# SCH_AD741-discrete_2022-10-03.net
KiCad netlist of a schematic drawn in EasyEDA
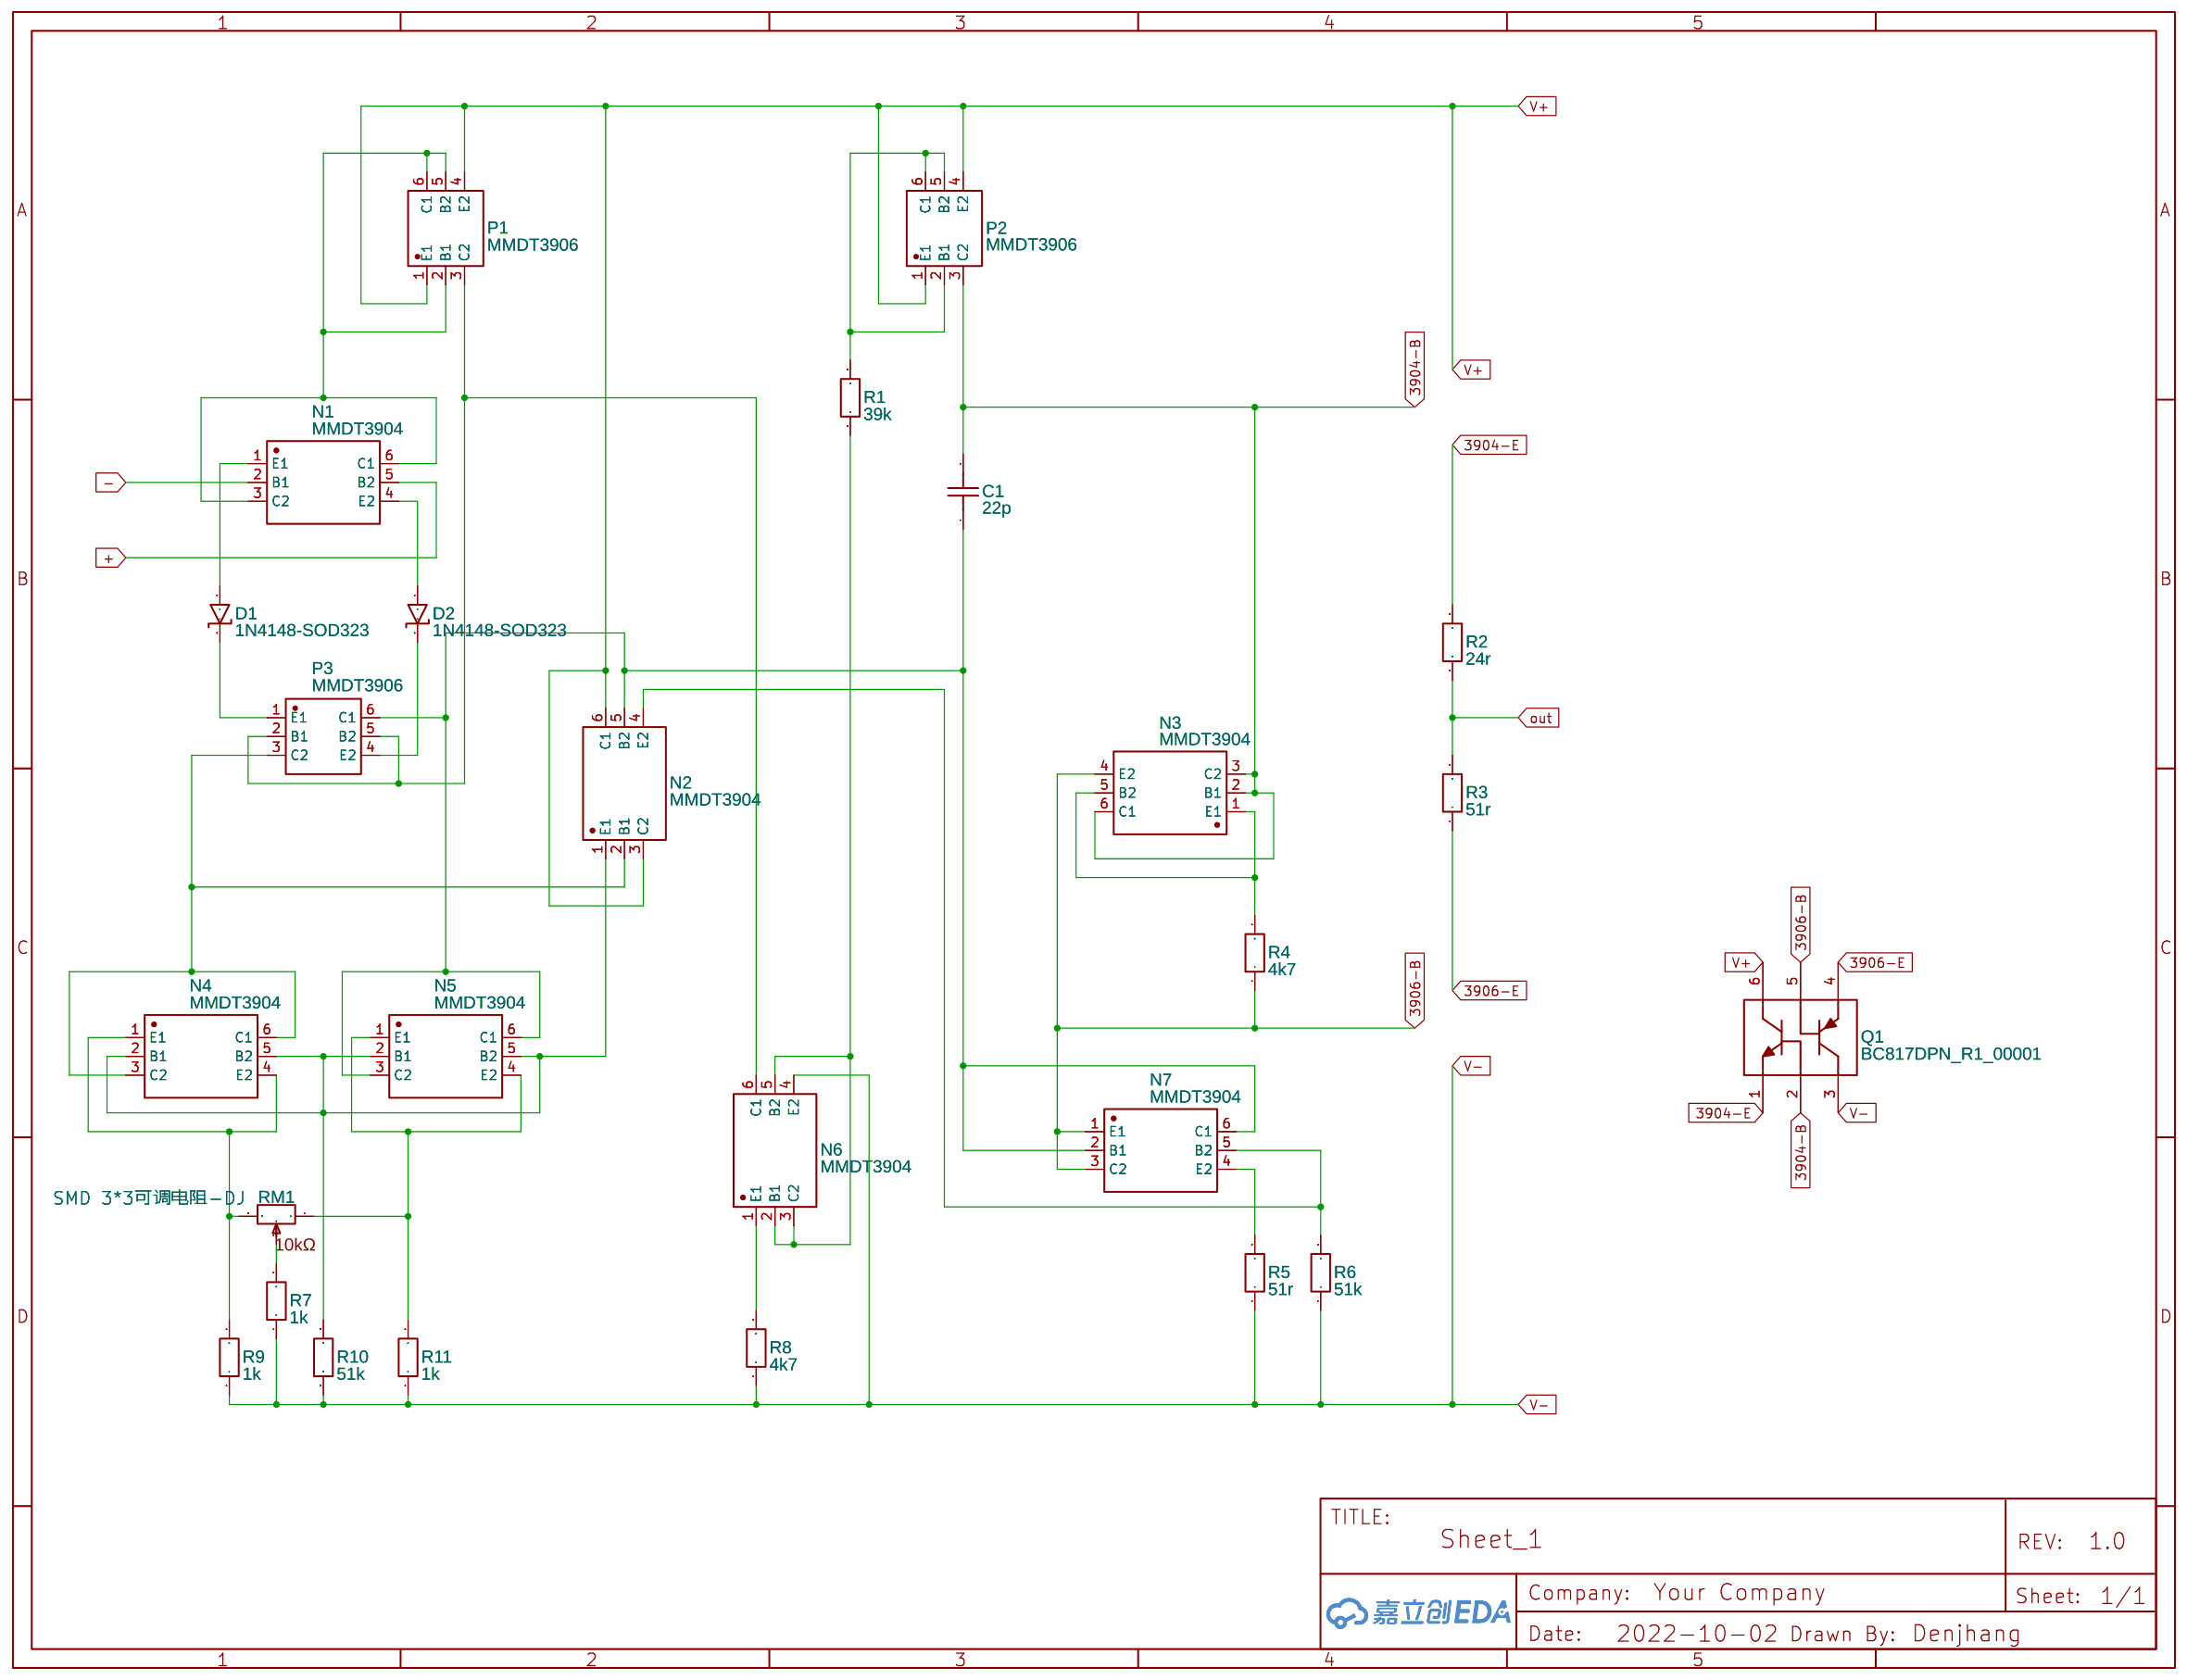
[diagram p0: P1]
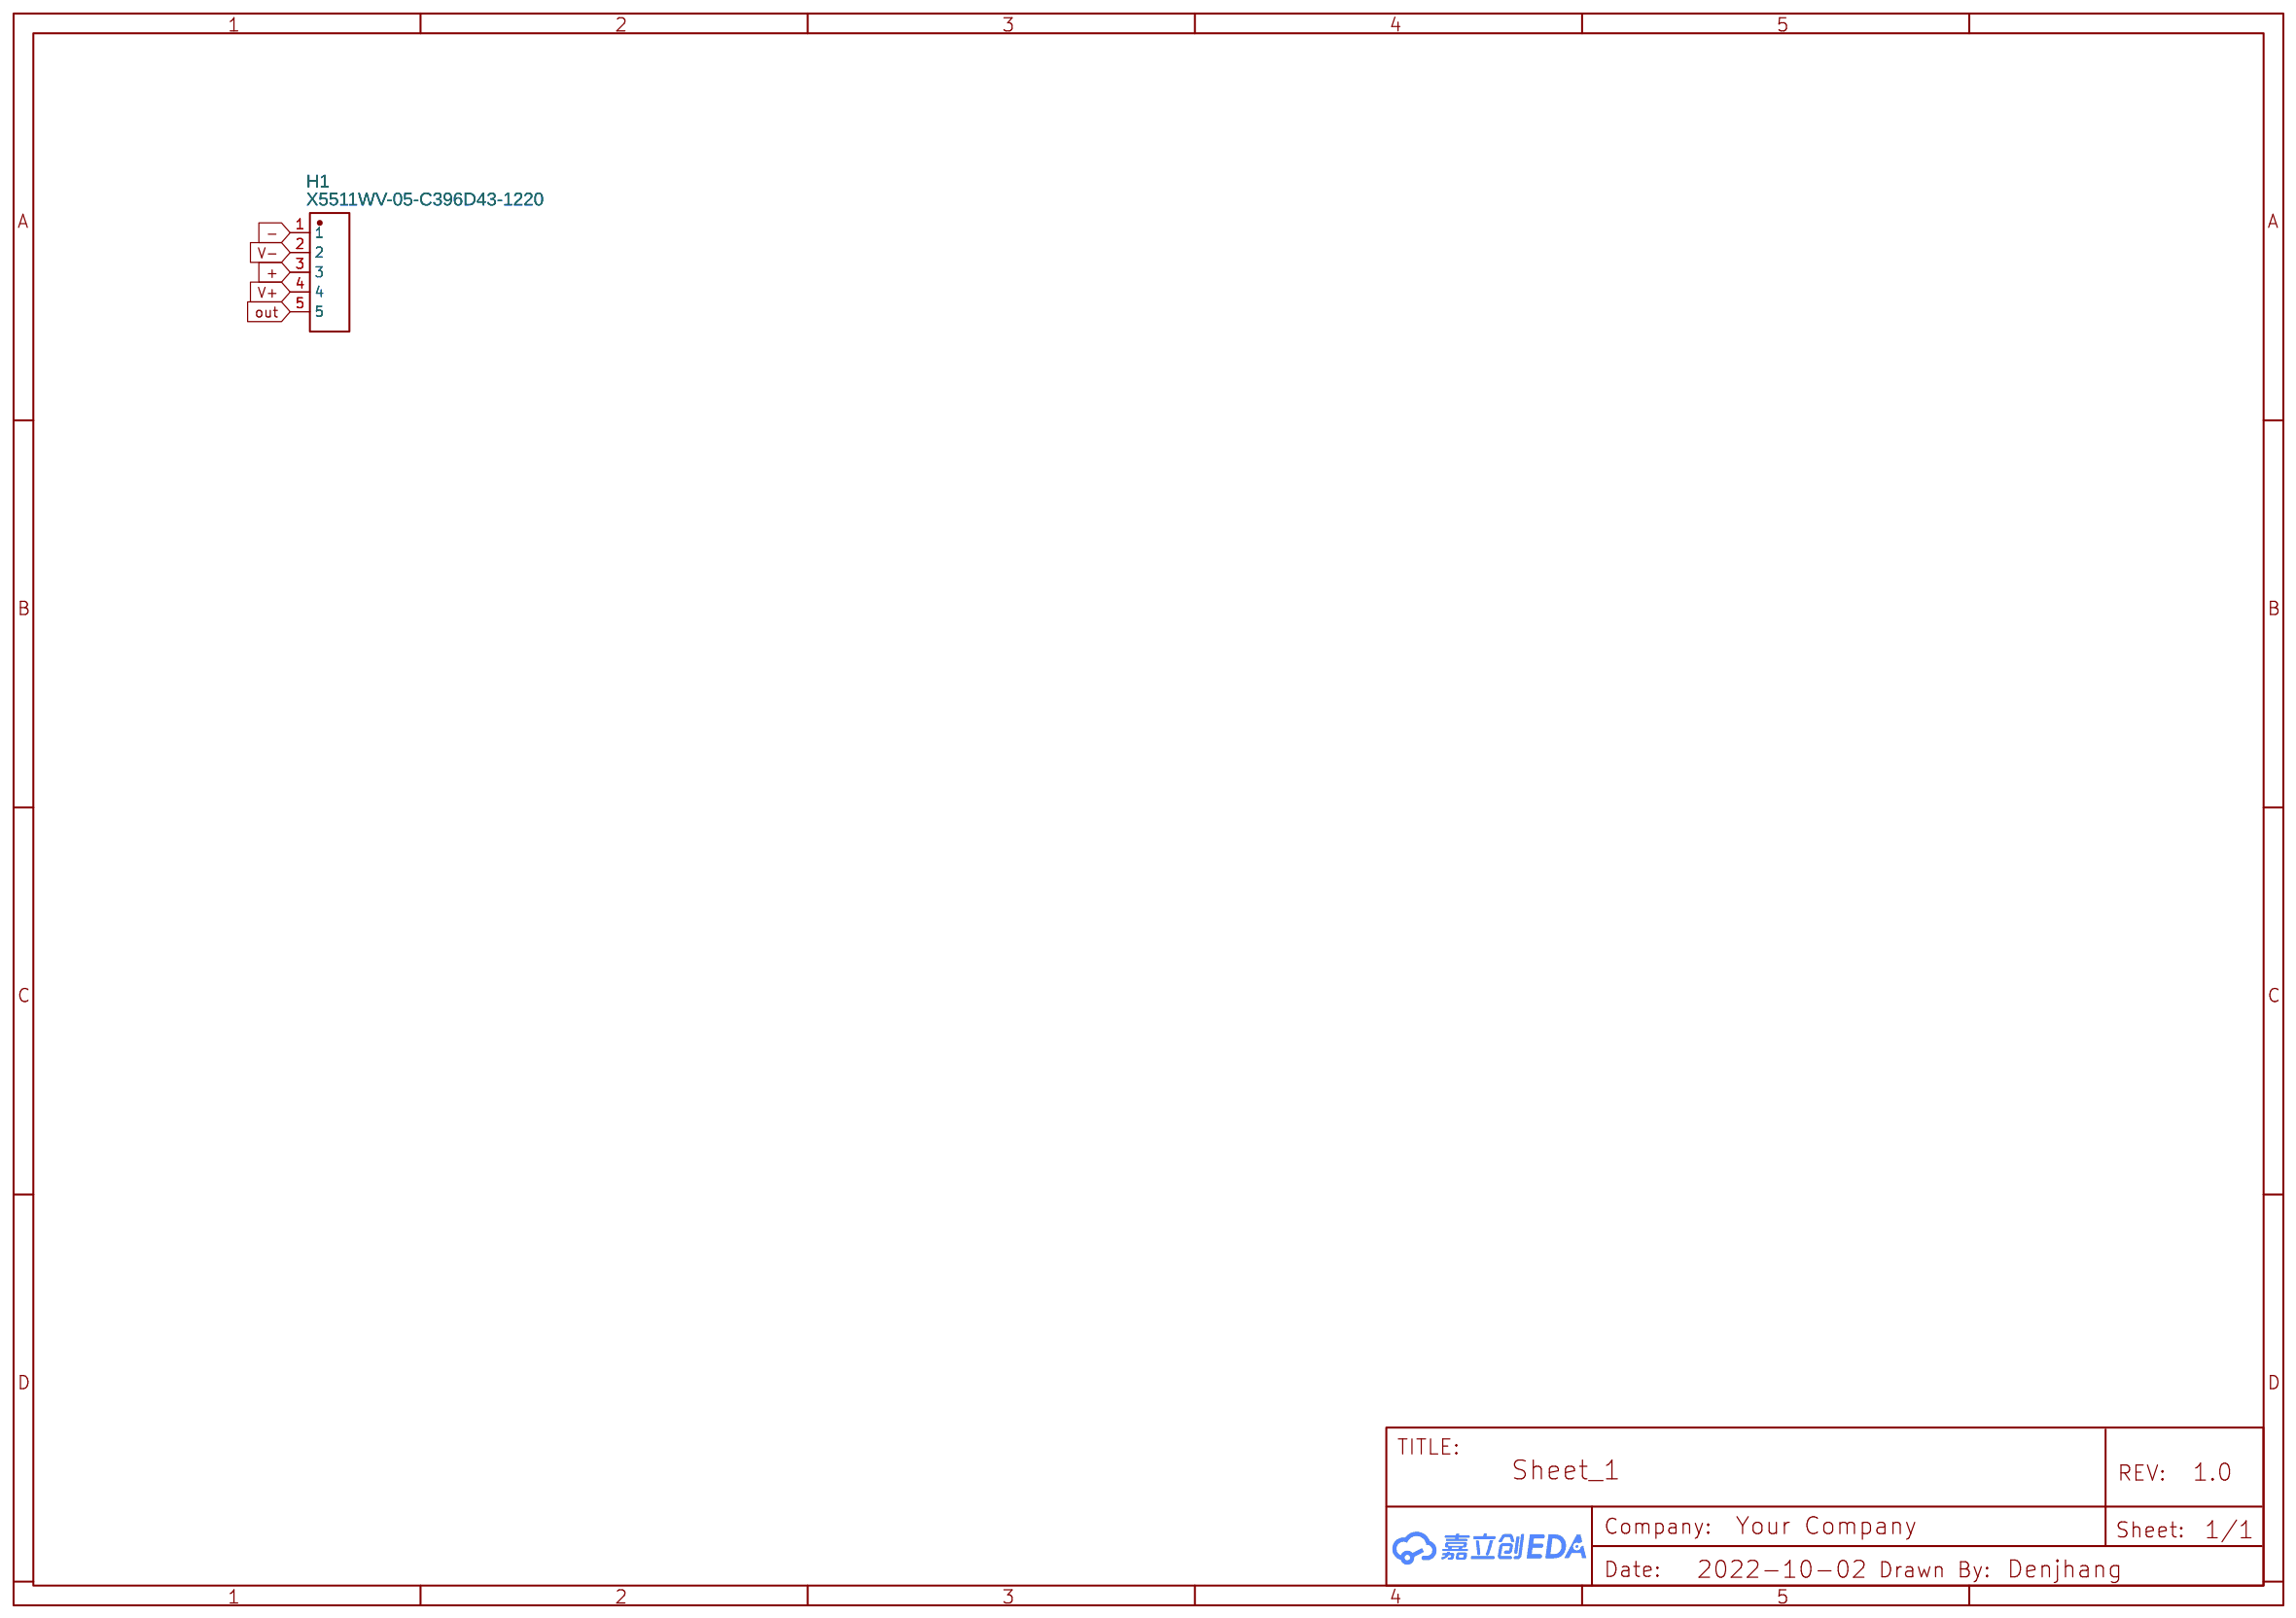
[diagram p1: CONN]

(export (version "E")
  (design (tool "Eeschema 10.0.6"))
  (components
    (comp (ref "C1") (value "22p") (libsource (lib "") (part "C_0603_US")))
    (comp (ref "D1")
      (value "1N4148-SOD323")
      (fields (field (name "BOM_Supplier Part") "C9900014362"))
      (libsource (lib "") (part "1N4148-SOD323"))
    )
    (comp (ref "D2")
      (value "1N4148-SOD323")
      (fields (field (name "BOM_Supplier Part") "C9900014362"))
      (libsource (lib "") (part "1N4148-SOD323"))
    )
    (comp (ref "N1")
      (value "MMDT3904")
      (fields (field (name "BOM_Supplier Part") "C21664"))
      (libsource (lib "") (part "MMDT3904"))
    )
    (comp (ref "N2")
      (value "MMDT3904")
      (fields (field (name "BOM_Supplier Part") "C21664"))
      (libsource (lib "") (part "MMDT3904_1"))
    )
    (comp (ref "N3")
      (value "MMDT3904")
      (fields (field (name "BOM_Supplier Part") "C21664"))
      (libsource (lib "") (part "MMDT3904_2"))
    )
    (comp (ref "N4")
      (value "MMDT3904")
      (fields (field (name "BOM_Supplier Part") "C21664"))
      (libsource (lib "") (part "MMDT3904"))
    )
    (comp (ref "N5")
      (value "MMDT3904")
      (fields (field (name "BOM_Supplier Part") "C21664"))
      (libsource (lib "") (part "MMDT3904"))
    )
    (comp (ref "N6")
      (value "MMDT3904")
      (fields (field (name "BOM_Supplier Part") "C21664"))
      (libsource (lib "") (part "MMDT3904_1"))
    )
    (comp (ref "N7")
      (value "MMDT3904")
      (fields (field (name "BOM_Supplier Part") "C21664"))
      (libsource (lib "") (part "MMDT3904"))
    )
    (comp (ref "P1")
      (value "MMDT3906")
      (fields (field (name "BOM_Supplier Part") "C20534"))
      (libsource (lib "") (part "MMDT3906"))
    )
    (comp (ref "P2")
      (value "MMDT3906")
      (fields (field (name "BOM_Supplier Part") "C20534"))
      (libsource (lib "") (part "MMDT3906"))
    )
    (comp (ref "P3")
      (value "MMDT3906")
      (fields (field (name "BOM_Supplier Part") "C20534"))
      (libsource (lib "") (part "MMDT3906_1"))
    )
    (comp (ref "Q1")
      (value "BC817DPN_R1_00001")
      (fields (field (name "BOM_Supplier Part") "C696397"))
      (libsource (lib "") (part "BC817DPN_R1_00001"))
    )
    (comp (ref "R1") (value "39k") (libsource (lib "") (part "R_0603_EU")))
    (comp (ref "R2") (value "24r") (libsource (lib "") (part "R_0603_EU")))
    (comp (ref "R3") (value "51r") (libsource (lib "") (part "R_0603_EU")))
    (comp (ref "R4") (value "4k7") (libsource (lib "") (part "R_0603_EU")))
    (comp (ref "R5") (value "51r") (libsource (lib "") (part "R_0603_EU")))
    (comp (ref "R6") (value "51k") (libsource (lib "") (part "R_0603_EU")))
    (comp (ref "R7") (value "1k") (libsource (lib "") (part "R_0603_EU")))
    (comp (ref "R8") (value "4k7") (libsource (lib "") (part "R_0603_EU")))
    (comp (ref "R9") (value "1k") (libsource (lib "") (part "R_0603_EU")))
    (comp (ref "R10") (value "51k") (libsource (lib "") (part "R_0603_EU")))
    (comp (ref "R11") (value "1k") (libsource (lib "") (part "R_0603_EU")))
    (comp (ref "RM1") (value "SMD 3*3可调电阻-DJ") (libsource (lib "") (part "SMD 3*3可调电阻-DJ")))
    (comp (ref "H1")
      (value "X5511WV-05-C396D43-1220")
      (fields (field (name "BOM_Supplier Part") "C2883392"))
      (libsource (lib "") (part "X5511WV-05-C396D43-1220"))
    )
  )
  (nets
    (net (code "1") (name "+") (class "Default")
      (node (ref "H1") (pin "3") (pinfunction "3_3") (pintype "unspecified"))
      (node (ref "N1") (pin "5") (pinfunction "B2_5") (pintype "unspecified"))
    )
    (net (code "2") (name "-") (class "Default")
      (node (ref "H1") (pin "1") (pinfunction "1_1") (pintype "unspecified"))
      (node (ref "N1") (pin "2") (pinfunction "B1_2") (pintype "unspecified"))
    )
    (net (code "3") (name "3904-B") (class "Default")
      (node (ref "C1") (pin "2") (pinfunction "2_2") (pintype "unspecified"))
      (node (ref "N3") (pin "2") (pinfunction "B1_2") (pintype "unspecified"))
      (node (ref "N3") (pin "3") (pinfunction "C2_3") (pintype "unspecified"))
      (node (ref "N3") (pin "6") (pinfunction "C1_6") (pintype "unspecified"))
      (node (ref "P2") (pin "3") (pinfunction "C2_3") (pintype "unspecified"))
      (node (ref "Q1") (pin "2") (pinfunction "B1_2") (pintype "unspecified"))
    )
    (net (code "4") (name "3904-E") (class "Default")
      (node (ref "Q1") (pin "1") (pinfunction "E1_1") (pintype "unspecified"))
      (node (ref "R2") (pin "2") (pinfunction "2_2") (pintype "unspecified"))
    )
    (net (code "5") (name "3906-B") (class "Default")
      (node (ref "N3") (pin "4") (pinfunction "E2_4") (pintype "unspecified"))
      (node (ref "N7") (pin "1") (pinfunction "E1_1") (pintype "unspecified"))
      (node (ref "N7") (pin "3") (pinfunction "C2_3") (pintype "unspecified"))
      (node (ref "Q1") (pin "5") (pinfunction "B2_5") (pintype "unspecified"))
      (node (ref "R4") (pin "1") (pinfunction "1_1") (pintype "unspecified"))
    )
    (net (code "6") (name "3906-E") (class "Default")
      (node (ref "Q1") (pin "4") (pinfunction "E2_4") (pintype "unspecified"))
      (node (ref "R3") (pin "1") (pinfunction "1_1") (pintype "unspecified"))
    )
    (net (code "7") (name "Net-(D1-A)") (class "Default")
      (node (ref "D1") (pin "1") (pinfunction "A_1") (pintype "unspecified"))
      (node (ref "N1") (pin "1") (pinfunction "E1_1") (pintype "unspecified"))
    )
    (net (code "8") (name "Net-(D1-K)") (class "Default")
      (node (ref "D1") (pin "2") (pinfunction "K_2") (pintype "unspecified"))
      (node (ref "P3") (pin "1") (pinfunction "E1_1") (pintype "unspecified"))
    )
    (net (code "9") (name "Net-(D2-A)") (class "Default")
      (node (ref "D2") (pin "1") (pinfunction "A_1") (pintype "unspecified"))
      (node (ref "N1") (pin "4") (pinfunction "E2_4") (pintype "unspecified"))
    )
    (net (code "10") (name "Net-(D2-K)") (class "Default")
      (node (ref "D2") (pin "2") (pinfunction "K_2") (pintype "unspecified"))
      (node (ref "P3") (pin "4") (pinfunction "E2_4") (pintype "unspecified"))
    )
    (net (code "11") (name "Net-(N1-C1)") (class "Default")
      (node (ref "N1") (pin "3") (pinfunction "C2_3") (pintype "unspecified"))
      (node (ref "N1") (pin "6") (pinfunction "C1_6") (pintype "unspecified"))
      (node (ref "P1") (pin "2") (pinfunction "B1_2") (pintype "unspecified"))
      (node (ref "P1") (pin "5") (pinfunction "B2_5") (pintype "unspecified"))
      (node (ref "P1") (pin "6") (pinfunction "C1_6") (pintype "unspecified"))
    )
    (net (code "12") (name "Net-(N2-B1)") (class "Default")
      (node (ref "N2") (pin "2") (pinfunction "B1_2") (pintype "unspecified"))
      (node (ref "N4") (pin "3") (pinfunction "C2_3") (pintype "unspecified"))
      (node (ref "N4") (pin "6") (pinfunction "C1_6") (pintype "unspecified"))
      (node (ref "P3") (pin "3") (pinfunction "C2_3") (pintype "unspecified"))
    )
    (net (code "13") (name "Net-(N2-B2)") (class "Default")
      (node (ref "C1") (pin "1") (pinfunction "1_1") (pintype "unspecified"))
      (node (ref "N2") (pin "5") (pinfunction "B2_5") (pintype "unspecified"))
      (node (ref "N5") (pin "3") (pinfunction "C2_3") (pintype "unspecified"))
      (node (ref "N5") (pin "6") (pinfunction "C1_6") (pintype "unspecified"))
      (node (ref "N7") (pin "2") (pinfunction "B1_2") (pintype "unspecified"))
      (node (ref "N7") (pin "6") (pinfunction "C1_6") (pintype "unspecified"))
      (node (ref "P3") (pin "6") (pinfunction "C1_6") (pintype "unspecified"))
    )
    (net (code "14") (name "Net-(N2-E1)") (class "Default")
      (node (ref "N2") (pin "1") (pinfunction "E1_1") (pintype "unspecified"))
      (node (ref "N4") (pin "2") (pinfunction "B1_2") (pintype "unspecified"))
      (node (ref "N4") (pin "5") (pinfunction "B2_5") (pintype "unspecified"))
      (node (ref "N5") (pin "2") (pinfunction "B1_2") (pintype "unspecified"))
      (node (ref "N5") (pin "5") (pinfunction "B2_5") (pintype "unspecified"))
      (node (ref "R10") (pin "2") (pinfunction "2_2") (pintype "unspecified"))
    )
    (net (code "15") (name "Net-(N2-E2)") (class "Default")
      (node (ref "N2") (pin "4") (pinfunction "E2_4") (pintype "unspecified"))
      (node (ref "N7") (pin "5") (pinfunction "B2_5") (pintype "unspecified"))
      (node (ref "R6") (pin "2") (pinfunction "2_2") (pintype "unspecified"))
    )
    (net (code "16") (name "Net-(N3-B2)") (class "Default")
      (node (ref "N3") (pin "1") (pinfunction "E1_1") (pintype "unspecified"))
      (node (ref "N3") (pin "5") (pinfunction "B2_5") (pintype "unspecified"))
      (node (ref "R4") (pin "2") (pinfunction "2_2") (pintype "unspecified"))
    )
    (net (code "17") (name "Net-(N4-E1)") (class "Default")
      (node (ref "N4") (pin "1") (pinfunction "E1_1") (pintype "unspecified"))
      (node (ref "N4") (pin "4") (pinfunction "E2_4") (pintype "unspecified"))
      (node (ref "R9") (pin "2") (pinfunction "2_2") (pintype "unspecified"))
      (node (ref "RM1") (pin "3") (pinfunction "3_3") (pintype "input"))
    )
    (net (code "18") (name "Net-(N5-E1)") (class "Default")
      (node (ref "N5") (pin "1") (pinfunction "E1_1") (pintype "unspecified"))
      (node (ref "N5") (pin "4") (pinfunction "E2_4") (pintype "unspecified"))
      (node (ref "R11") (pin "2") (pinfunction "2_2") (pintype "unspecified"))
      (node (ref "RM1") (pin "1") (pinfunction "1_1") (pintype "input"))
    )
    (net (code "19") (name "Net-(N6-B1)") (class "Default")
      (node (ref "N6") (pin "2") (pinfunction "B1_2") (pintype "unspecified"))
      (node (ref "N6") (pin "3") (pinfunction "C2_3") (pintype "unspecified"))
      (node (ref "N6") (pin "5") (pinfunction "B2_5") (pintype "unspecified"))
      (node (ref "R1") (pin "1") (pinfunction "1_1") (pintype "unspecified"))
    )
    (net (code "20") (name "Net-(N6-C1)") (class "Default")
      (node (ref "N6") (pin "6") (pinfunction "C1_6") (pintype "unspecified"))
      (node (ref "P1") (pin "3") (pinfunction "C2_3") (pintype "unspecified"))
      (node (ref "P3") (pin "2") (pinfunction "B1_2") (pintype "unspecified"))
      (node (ref "P3") (pin "5") (pinfunction "B2_5") (pintype "unspecified"))
    )
    (net (code "21") (name "Net-(N6-E1)") (class "Default")
      (node (ref "N6") (pin "1") (pinfunction "E1_1") (pintype "unspecified"))
      (node (ref "R8") (pin "2") (pinfunction "2_2") (pintype "unspecified"))
    )
    (net (code "22") (name "Net-(N7-E2)") (class "Default")
      (node (ref "N7") (pin "4") (pinfunction "E2_4") (pintype "unspecified"))
      (node (ref "R5") (pin "2") (pinfunction "2_2") (pintype "unspecified"))
    )
    (net (code "23") (name "Net-(P2-B1)") (class "Default")
      (node (ref "P2") (pin "2") (pinfunction "B1_2") (pintype "unspecified"))
      (node (ref "P2") (pin "5") (pinfunction "B2_5") (pintype "unspecified"))
      (node (ref "P2") (pin "6") (pinfunction "C1_6") (pintype "unspecified"))
      (node (ref "R1") (pin "2") (pinfunction "2_2") (pintype "unspecified"))
    )
    (net (code "24") (name "Net-(R7-Pad2)") (class "Default")
      (node (ref "R7") (pin "2") (pinfunction "2_2") (pintype "unspecified"))
      (node (ref "RM1") (pin "2") (pinfunction "2_2") (pintype "input"))
    )
    (net (code "25") (name "V+") (class "Default")
      (node (ref "H1") (pin "4") (pinfunction "4_4") (pintype "unspecified"))
      (node (ref "N2") (pin "3") (pinfunction "C2_3") (pintype "unspecified"))
      (node (ref "N2") (pin "6") (pinfunction "C1_6") (pintype "unspecified"))
      (node (ref "P1") (pin "1") (pinfunction "E1_1") (pintype "unspecified"))
      (node (ref "P1") (pin "4") (pinfunction "E2_4") (pintype "unspecified"))
      (node (ref "P2") (pin "1") (pinfunction "E1_1") (pintype "unspecified"))
      (node (ref "P2") (pin "4") (pinfunction "E2_4") (pintype "unspecified"))
      (node (ref "Q1") (pin "6") (pinfunction "C1_6") (pintype "unspecified"))
    )
    (net (code "26") (name "V-") (class "Default")
      (node (ref "H1") (pin "2") (pinfunction "2_2") (pintype "unspecified"))
      (node (ref "N6") (pin "4") (pinfunction "E2_4") (pintype "unspecified"))
      (node (ref "Q1") (pin "3") (pinfunction "C2_3") (pintype "unspecified"))
      (node (ref "R10") (pin "1") (pinfunction "1_1") (pintype "unspecified"))
      (node (ref "R11") (pin "1") (pinfunction "1_1") (pintype "unspecified"))
      (node (ref "R5") (pin "1") (pinfunction "1_1") (pintype "unspecified"))
      (node (ref "R6") (pin "1") (pinfunction "1_1") (pintype "unspecified"))
      (node (ref "R7") (pin "1") (pinfunction "1_1") (pintype "unspecified"))
      (node (ref "R8") (pin "1") (pinfunction "1_1") (pintype "unspecified"))
      (node (ref "R9") (pin "1") (pinfunction "1_1") (pintype "unspecified"))
    )
    (net (code "27") (name "out") (class "Default")
      (node (ref "H1") (pin "5") (pinfunction "5_5") (pintype "unspecified"))
      (node (ref "R2") (pin "1") (pinfunction "1_1") (pintype "unspecified"))
      (node (ref "R3") (pin "2") (pinfunction "2_2") (pintype "unspecified"))
    )
  )
)
